# EMT-_Exciting_Source.net
KiCad netlist of a schematic drawn in Altium Designer
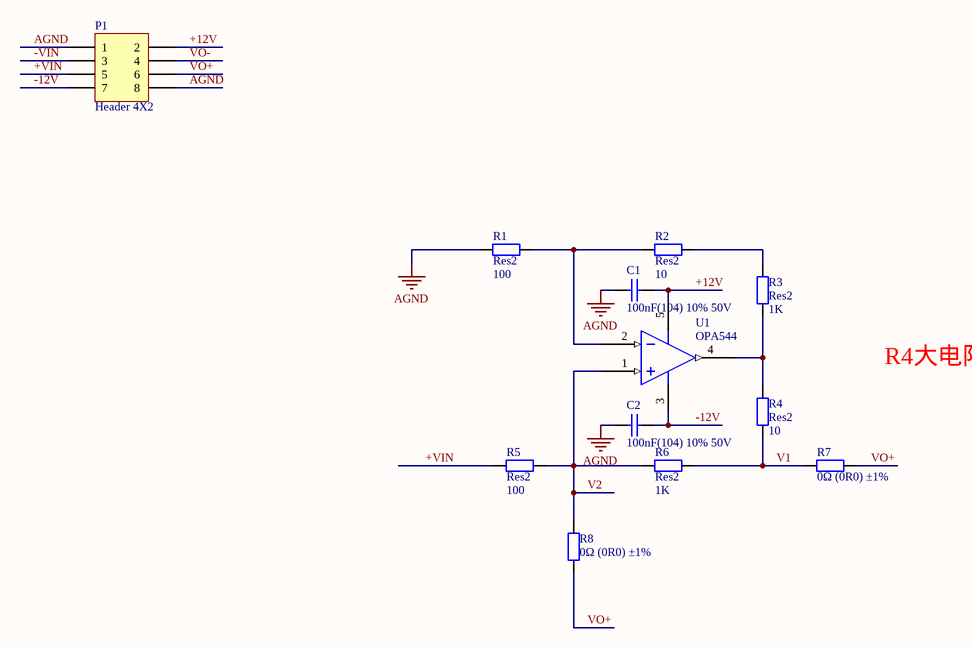
[diagram p0: EMT- Exciting Source.SchDoc]

(export (version "E")
  (design (tool "Eeschema 10.0.6"))
  (components
    (comp (ref "C1")
      (value "100nF(104) 10% 50V")
      (footprint "LC-0805_C")
      (description "贴片电容")
      (libsource (lib "Miscellaneous Devices LC") (part "0805 100nF(104) 10% 50V"))
    )
    (comp (ref "C2")
      (value "100nF(104) 10% 50V")
      (footprint "LC-0805_C")
      (description "贴片电容")
      (libsource (lib "Miscellaneous Devices LC") (part "0805 100nF(104) 10% 50V"))
    )
    (comp (ref "P1")
      (value "Header 4X2")
      (footprint "HDR2X4")
      (description "Header, 4-Pin, Dual row")
      (fields (field (name "PUBLISHER") "Altium Limited"))
      (libsource (lib "Miscellaneous Connectors") (part "Header 4X2"))
    )
    (comp (ref "R1")
      (value "Res2")
      (footprint "AXIAL-0.4")
      (description "Resistor")
      (fields (field (name "ALTIUM_VALUE") "100") (field (name "PUBLISHER") "Altium Limited"))
      (libsource (lib "Miscellaneous Devices") (part "Res2"))
    )
    (comp (ref "R2")
      (value "Res2")
      (footprint "AXIAL-0.4")
      (description "Resistor")
      (fields (field (name "ALTIUM_VALUE") "10") (field (name "PUBLISHER") "Altium Limited"))
      (libsource (lib "Miscellaneous Devices") (part "Res2"))
    )
    (comp (ref "R3")
      (value "Res2")
      (footprint "AXIAL-0.4")
      (description "Resistor")
      (fields (field (name "ALTIUM_VALUE") "1K") (field (name "PUBLISHER") "Altium Limited"))
      (libsource (lib "") (part "Res2_1"))
    )
    (comp (ref "R4")
      (value "Res2")
      (footprint "AXIAL-0.4")
      (description "Resistor")
      (fields (field (name "ALTIUM_VALUE") "10") (field (name "PUBLISHER") "Altium Limited"))
      (libsource (lib "") (part "Res2_1"))
    )
    (comp (ref "R5")
      (value "Res2")
      (footprint "AXIAL-0.4")
      (description "Resistor")
      (fields (field (name "ALTIUM_VALUE") "100") (field (name "PUBLISHER") "Altium Limited"))
      (libsource (lib "Miscellaneous Devices") (part "Res2"))
    )
    (comp (ref "R6")
      (value "Res2")
      (footprint "AXIAL-0.4")
      (description "Resistor")
      (fields (field (name "ALTIUM_VALUE") "1K") (field (name "PUBLISHER") "Altium Limited"))
      (libsource (lib "Miscellaneous Devices") (part "Res2"))
    )
    (comp (ref "R7")
      (value "0Ω (0R0) ±1%")
      (footprint "LC-0805_R")
      (description "贴片电阻")
      (libsource (lib "") (part "0805 0Ω (0R0) 1%_1"))
    )
    (comp (ref "R8")
      (value "0Ω (0R0) ±1%")
      (footprint "LC-0805_R")
      (description "贴片电阻")
      (libsource (lib "Miscellaneous Devices LC") (part "0805 0Ω (0R0) 1%"))
    )
    (comp (ref "U1")
      (value "OPA544")
      (footprint "TO-220-5")
      (description "Imported")
      (fields
        (field (name "MANUFACTURER") "Texas Instruments")
        (field (name "MANUFACTURER_PART_NUMBER") "opa544_ktt_5")
      )
      (libsource (lib "OPA544") (part "OPA544"))
    )
  )
  (nets
    (net (code "1") (name "/+12V") (class "Default")
      (node (ref "C1") (pin "2") (pinfunction "2_2") (pintype "passive"))
      (node (ref "P1") (pin "2") (pinfunction "2_2") (pintype "passive"))
      (node (ref "U1") (pin "5") (pinfunction "+VS_5") (pintype "power_in"))
    )
    (net (code "2") (name "/+VIN") (class "Default")
      (node (ref "P1") (pin "5") (pinfunction "5_5") (pintype "passive"))
      (node (ref "R5") (pin "1") (pinfunction "1_1") (pintype "passive"))
    )
    (net (code "3") (name "/-12V") (class "Default")
      (node (ref "C2") (pin "2") (pinfunction "2_2") (pintype "passive"))
      (node (ref "P1") (pin "7") (pinfunction "7_7") (pintype "passive"))
      (node (ref "U1") (pin "3") (pinfunction "-VS_3") (pintype "power_in"))
    )
    (net (code "4") (name "/-VIN") (class "Default")
      (node (ref "P1") (pin "3") (pinfunction "3_3") (pintype "passive"))
    )
    (net (code "5") (name "/V1") (class "Default")
      (node (ref "R4") (pin "1") (pinfunction "1_1") (pintype "passive"))
      (node (ref "R6") (pin "2") (pinfunction "2_2") (pintype "passive"))
      (node (ref "R7") (pin "1") (pinfunction "1_1") (pintype "passive"))
    )
    (net (code "6") (name "/V2") (class "Default")
      (node (ref "R5") (pin "2") (pinfunction "2_2") (pintype "passive"))
      (node (ref "R6") (pin "1") (pinfunction "1_1") (pintype "passive"))
      (node (ref "R8") (pin "2") (pinfunction "2_2") (pintype "passive"))
      (node (ref "U1") (pin "1") (pinfunction "+_1") (pintype "input"))
    )
    (net (code "7") (name "/VO+") (class "Default")
      (node (ref "P1") (pin "6") (pinfunction "6_6") (pintype "passive"))
      (node (ref "R7") (pin "2") (pinfunction "2_2") (pintype "passive"))
      (node (ref "R8") (pin "1") (pinfunction "1_1") (pintype "passive"))
    )
    (net (code "8") (name "/VO-") (class "Default")
      (node (ref "P1") (pin "4") (pinfunction "4_4") (pintype "passive"))
    )
    (net (code "9") (name "AGND") (class "Default")
      (node (ref "C1") (pin "1") (pinfunction "1_1") (pintype "passive"))
      (node (ref "C2") (pin "1") (pinfunction "1_1") (pintype "passive"))
      (node (ref "P1") (pin "1") (pinfunction "1_1") (pintype "passive"))
      (node (ref "P1") (pin "8") (pinfunction "8_8") (pintype "passive"))
      (node (ref "R1") (pin "1") (pinfunction "1_1") (pintype "passive"))
    )
    (net (code "10") (name "Net-(R2-Pad2)") (class "Default")
      (node (ref "R2") (pin "2") (pinfunction "2_2") (pintype "passive"))
      (node (ref "R3") (pin "2") (pinfunction "2_2") (pintype "passive"))
    )
    (net (code "11") (name "Net-(U1--)") (class "Default")
      (node (ref "R1") (pin "2") (pinfunction "2_2") (pintype "passive"))
      (node (ref "R2") (pin "1") (pinfunction "1_1") (pintype "passive"))
      (node (ref "U1") (pin "2") (pinfunction "-_2") (pintype "input"))
    )
    (net (code "12") (name "Net-(U1-VO)") (class "Default")
      (node (ref "R3") (pin "1") (pinfunction "1_1") (pintype "passive"))
      (node (ref "R4") (pin "2") (pinfunction "2_2") (pintype "passive"))
      (node (ref "U1") (pin "4") (pinfunction "VO_4") (pintype "output"))
    )
  )
)
